# RF.net
KiCad netlist of a schematic drawn in Altium Designer
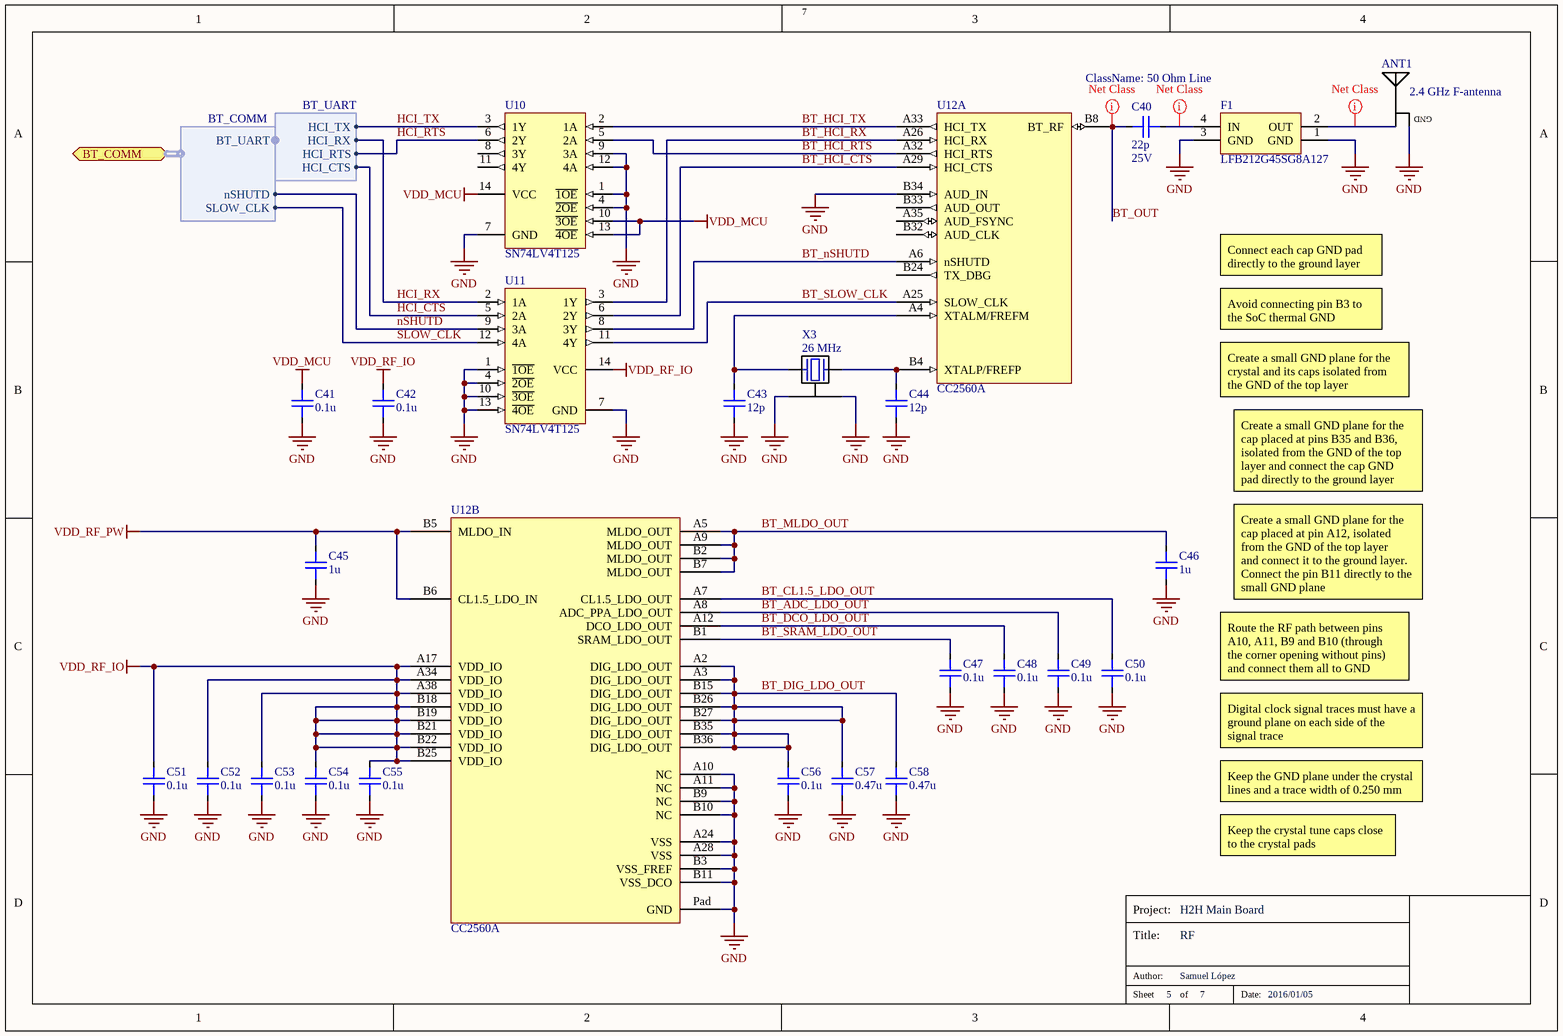
[diagram p0: RF.SchDoc]

(export (version "E")
  (design (tool "Eeschema 10.0.6"))
  (components
    (comp (ref "ANT1")
      (value "2.4 GHz F-antenna")
      (footprint "Antenna Inverted F 2.4 GHz")
      (description "Antenna - Inverted F 2.4 GHz")
      (libsource (lib "H2H") (part "ANT 2.4 GHz"))
    )
    (comp (ref "C40")
      (value "22p")
      (footprint "C0402")
      (description "Capacitor")
      (fields (field (name "RATED VOLTAGE") "25V"))
      (libsource (lib "Misc") (part "Capacitor"))
    )
    (comp (ref "C41")
      (value "0.1u")
      (footprint "C0603")
      (description "Capacitor")
      (libsource (lib "Misc") (part "Capacitor"))
    )
    (comp (ref "C42")
      (value "0.1u")
      (footprint "C0603")
      (description "Capacitor")
      (libsource (lib "Misc") (part "Capacitor"))
    )
    (comp (ref "C43")
      (value "12p")
      (footprint "C0402")
      (description "Capacitor")
      (libsource (lib "Misc") (part "Capacitor"))
    )
    (comp (ref "C44")
      (value "12p")
      (footprint "C0402")
      (description "Capacitor")
      (libsource (lib "Misc") (part "Capacitor"))
    )
    (comp (ref "C45")
      (value "1u")
      (footprint "C0402")
      (description "Capacitor")
      (libsource (lib "Misc") (part "Capacitor"))
    )
    (comp (ref "C46")
      (value "1u")
      (footprint "C0402")
      (description "Capacitor")
      (libsource (lib "Misc") (part "Capacitor"))
    )
    (comp (ref "C47")
      (value "0.1u")
      (footprint "C0402")
      (description "Capacitor")
      (libsource (lib "Misc") (part "Capacitor"))
    )
    (comp (ref "C48")
      (value "0.1u")
      (footprint "C0402")
      (description "Capacitor")
      (libsource (lib "Misc") (part "Capacitor"))
    )
    (comp (ref "C49")
      (value "0.1u")
      (footprint "C0402")
      (description "Capacitor")
      (libsource (lib "Misc") (part "Capacitor"))
    )
    (comp (ref "C50")
      (value "0.1u")
      (footprint "C0402")
      (description "Capacitor")
      (libsource (lib "Misc") (part "Capacitor"))
    )
    (comp (ref "C51")
      (value "0.1u")
      (footprint "C0402")
      (description "Capacitor")
      (libsource (lib "Misc") (part "Capacitor"))
    )
    (comp (ref "C52")
      (value "0.1u")
      (footprint "C0402")
      (description "Capacitor")
      (libsource (lib "Misc") (part "Capacitor"))
    )
    (comp (ref "C53")
      (value "0.1u")
      (footprint "C0402")
      (description "Capacitor")
      (libsource (lib "Misc") (part "Capacitor"))
    )
    (comp (ref "C54")
      (value "0.1u")
      (footprint "C0402")
      (description "Capacitor")
      (libsource (lib "Misc") (part "Capacitor"))
    )
    (comp (ref "C55")
      (value "0.1u")
      (footprint "C0402")
      (description "Capacitor")
      (libsource (lib "Misc") (part "Capacitor"))
    )
    (comp (ref "C56")
      (value "0.1u")
      (footprint "C0402")
      (description "Capacitor")
      (libsource (lib "Misc") (part "Capacitor"))
    )
    (comp (ref "C57")
      (value "0.47u")
      (footprint "C0402")
      (description "Capacitor")
      (libsource (lib "Misc") (part "Capacitor"))
    )
    (comp (ref "C58")
      (value "0.47u")
      (footprint "C0402")
      (description "Capacitor")
      (libsource (lib "Misc") (part "Capacitor"))
    )
    (comp (ref "F1")
      (value "LFB212G45SG8A127")
      (footprint "LFB212G45SG8A127")
      (description "Filter - RF 2.4 GHz")
      (libsource (lib "H2H") (part "LFB212G45SG8A127"))
    )
    (comp (ref "U10")
      (value "SN74LV4T125")
      (footprint "SN74LV4T125")
      (description "IC - Voltage Level Translator")
      (libsource (lib "") (part "SN74LV4T125_1"))
    )
    (comp (ref "U11")
      (value "SN74LV4T125")
      (footprint "SN74LV4T125")
      (description "IC - Voltage Level Translator")
      (libsource (lib "H2H") (part "SN74LV4T125"))
    )
    (comp (ref "U12")
      (value "CC2560A")
      (footprint "CC256x")
      (description "IC - Bluetooth 4.0 controller (BR/EDR)")
      (libsource (lib "H2H") (part "CC2560A"))
    )
    (comp (ref "X3")
      (value "NX2016SA")
      (footprint "NX2016SA")
      (description "Crystal - 26 MHz")
      (fields (field (name "FREQUENCY") "26 MHz"))
      (libsource (lib "H2H") (part "NX2016SA"))
    )
  )
  (nets
    (net (code "2") (name "/BT_ADC_LDO_OUT") (class "Default")
      (node (ref "C49") (pin "2") (pinfunction "2_2") (pintype "passive"))
      (node (ref "U12") (pin "A8") (pinfunction "ADC_PPA_LDO_OUT_A8") (pintype "power_in"))
    )
    (net (code "3") (name "/BT_CL1.5_LDO_OUT") (class "Default")
      (node (ref "C50") (pin "2") (pinfunction "2_2") (pintype "passive"))
      (node (ref "U12") (pin "A7") (pinfunction "CL1.5_LDO_OUT_A7") (pintype "power_in"))
    )
    (net (code "4") (name "/BT_DCO_LDO_OUT") (class "Default")
      (node (ref "C48") (pin "2") (pinfunction "2_2") (pintype "passive"))
      (node (ref "U12") (pin "A12") (pinfunction "DCO_LDO_OUT_A12") (pintype "power_in"))
    )
    (net (code "5") (name "/BT_DIG_LDO_OUT") (class "Default")
      (node (ref "C56") (pin "2") (pinfunction "2_2") (pintype "passive"))
      (node (ref "C57") (pin "2") (pinfunction "2_2") (pintype "passive"))
      (node (ref "C58") (pin "2") (pinfunction "2_2") (pintype "passive"))
      (node (ref "U12") (pin "A2") (pinfunction "DIG_LDO_OUT_A2") (pintype "power_in"))
      (node (ref "U12") (pin "A3") (pinfunction "DIG_LDO_OUT_A3") (pintype "power_in"))
      (node (ref "U12") (pin "B15") (pinfunction "DIG_LDO_OUT_B15") (pintype "power_in"))
      (node (ref "U12") (pin "B26") (pinfunction "DIG_LDO_OUT_B26") (pintype "power_in"))
      (node (ref "U12") (pin "B27") (pinfunction "DIG_LDO_OUT_B27") (pintype "power_in"))
      (node (ref "U12") (pin "B35") (pinfunction "DIG_LDO_OUT_B35") (pintype "power_in"))
      (node (ref "U12") (pin "B36") (pinfunction "DIG_LDO_OUT_B36") (pintype "power_in"))
    )
    (net (code "6") (name "/BT_HCI_CTS") (class "Default")
      (node (ref "U11") (pin "6") (pinfunction "2Y_6") (pintype "output"))
      (node (ref "U12") (pin "A29") (pinfunction "HCI_CTS_A29") (pintype "input"))
    )
    (net (code "7") (name "/BT_HCI_RTS") (class "Default")
      (node (ref "U10") (pin "5") (pinfunction "2A_5") (pintype "input"))
      (node (ref "U12") (pin "A32") (pinfunction "HCI_RTS_A32") (pintype "output"))
    )
    (net (code "8") (name "/BT_HCI_RX") (class "Default")
      (node (ref "U11") (pin "3") (pinfunction "1Y_3") (pintype "output"))
      (node (ref "U12") (pin "A26") (pinfunction "HCI_RX_A26") (pintype "input"))
    )
    (net (code "9") (name "/BT_HCI_TX") (class "Default")
      (node (ref "U10") (pin "2") (pinfunction "1A_2") (pintype "input"))
      (node (ref "U12") (pin "A33") (pinfunction "HCI_TX_A33") (pintype "output"))
    )
    (net (code "10") (name "/BT_MLDO_OUT") (class "Default")
      (node (ref "C46") (pin "2") (pinfunction "2_2") (pintype "passive"))
      (node (ref "U12") (pin "A5") (pinfunction "MLDO_OUT_A5") (pintype "power_in"))
      (node (ref "U12") (pin "A9") (pinfunction "MLDO_OUT_A9") (pintype "power_in"))
      (node (ref "U12") (pin "B2") (pinfunction "MLDO_OUT_B2") (pintype "power_in"))
      (node (ref "U12") (pin "B7") (pinfunction "MLDO_OUT_B7") (pintype "power_in"))
    )
    (net (code "11") (name "/BT_OUT") (class "Default")
      (node (ref "C40") (pin "1") (pinfunction "1_1") (pintype "passive"))
      (node (ref "U12") (pin "B8") (pinfunction "BT_RF_B8") (pintype "bidirectional"))
    )
    (net (code "12") (name "/BT_SLOW_CLK") (class "Default")
      (node (ref "U11") (pin "11") (pinfunction "4Y_11") (pintype "output"))
      (node (ref "U12") (pin "A25") (pinfunction "SLOW_CLK_A25") (pintype "input"))
    )
    (net (code "13") (name "/BT_SRAM_LDO_OUT") (class "Default")
      (node (ref "C47") (pin "2") (pinfunction "2_2") (pintype "passive"))
      (node (ref "U12") (pin "B1") (pinfunction "SRAM_LDO_OUT_B1") (pintype "power_in"))
    )
    (net (code "14") (name "/BT_nSHUTD") (class "Default")
      (node (ref "U11") (pin "8") (pinfunction "3Y_8") (pintype "output"))
      (node (ref "U12") (pin "A6") (pinfunction "nSHUTD_A6") (pintype "input"))
    )
    (net (code "15") (name "/HCI_CTS") (class "Default")
      (node (ref "U11") (pin "5") (pinfunction "2A_5") (pintype "input"))
    )
    (net (code "16") (name "/HCI_RTS") (class "Default")
      (node (ref "U10") (pin "6") (pinfunction "2Y_6") (pintype "output"))
    )
    (net (code "17") (name "/HCI_RX") (class "Default")
      (node (ref "U11") (pin "2") (pinfunction "1A_2") (pintype "input"))
    )
    (net (code "18") (name "/HCI_TX") (class "Default")
      (node (ref "U10") (pin "3") (pinfunction "1Y_3") (pintype "output"))
    )
    (net (code "19") (name "/SLOW_CLK") (class "Default")
      (node (ref "U11") (pin "12") (pinfunction "4A_12") (pintype "input"))
    )
    (net (code "20") (name "/nSHUTD") (class "Default")
      (node (ref "U11") (pin "9") (pinfunction "3A_9") (pintype "input"))
    )
    (net (code "22") (name "GND") (class "Default")
      (node (ref "ANT1") (pin "2") (pinfunction "GND_2") (pintype "passive"))
      (node (ref "C41") (pin "1") (pinfunction "1_1") (pintype "passive"))
      (node (ref "C42") (pin "1") (pinfunction "1_1") (pintype "passive"))
      (node (ref "C43") (pin "1") (pinfunction "1_1") (pintype "passive"))
      (node (ref "C44") (pin "1") (pinfunction "1_1") (pintype "passive"))
      (node (ref "C45") (pin "1") (pinfunction "1_1") (pintype "passive"))
      (node (ref "C46") (pin "1") (pinfunction "1_1") (pintype "passive"))
      (node (ref "C47") (pin "1") (pinfunction "1_1") (pintype "passive"))
      (node (ref "C48") (pin "1") (pinfunction "1_1") (pintype "passive"))
      (node (ref "C49") (pin "1") (pinfunction "1_1") (pintype "passive"))
      (node (ref "C50") (pin "1") (pinfunction "1_1") (pintype "passive"))
      (node (ref "C51") (pin "1") (pinfunction "1_1") (pintype "passive"))
      (node (ref "C52") (pin "1") (pinfunction "1_1") (pintype "passive"))
      (node (ref "C53") (pin "1") (pinfunction "1_1") (pintype "passive"))
      (node (ref "C54") (pin "1") (pinfunction "1_1") (pintype "passive"))
      (node (ref "C55") (pin "1") (pinfunction "1_1") (pintype "passive"))
      (node (ref "C56") (pin "1") (pinfunction "1_1") (pintype "passive"))
      (node (ref "C57") (pin "1") (pinfunction "1_1") (pintype "passive"))
      (node (ref "C58") (pin "1") (pinfunction "1_1") (pintype "passive"))
      (node (ref "F1") (pin "1") (pinfunction "GND_1") (pintype "power_in"))
      (node (ref "F1") (pin "3") (pinfunction "GND_3") (pintype "power_in"))
      (node (ref "U10") (pin "1") (pinfunction "~{1OE}_1") (pintype "input"))
      (node (ref "U10") (pin "12") (pinfunction "4A_12") (pintype "input"))
      (node (ref "U10") (pin "4") (pinfunction "~{2OE}_4") (pintype "input"))
      (node (ref "U10") (pin "7") (pinfunction "GND_7") (pintype "power_in"))
      (node (ref "U10") (pin "9") (pinfunction "3A_9") (pintype "input"))
      (node (ref "U11") (pin "1") (pinfunction "~{1OE}_1") (pintype "input"))
      (node (ref "U11") (pin "10") (pinfunction "~{3OE}_10") (pintype "input"))
      (node (ref "U11") (pin "13") (pinfunction "~{4OE}_13") (pintype "input"))
      (node (ref "U11") (pin "4") (pinfunction "~{2OE}_4") (pintype "input"))
      (node (ref "U11") (pin "7") (pinfunction "GND_7") (pintype "power_in"))
      (node (ref "U12") (pin "A10") (pinfunction "NC_A10") (pintype "passive"))
      (node (ref "U12") (pin "A11") (pinfunction "NC_A11") (pintype "passive"))
      (node (ref "U12") (pin "A24") (pinfunction "VSS_A24") (pintype "power_in"))
      (node (ref "U12") (pin "A28") (pinfunction "VSS_A28") (pintype "power_in"))
      (node (ref "U12") (pin "B10") (pinfunction "NC_B10") (pintype "passive"))
      (node (ref "U12") (pin "B11") (pinfunction "VSS_DCO_B11") (pintype "power_in"))
      (node (ref "U12") (pin "B3") (pinfunction "VSS_FREF_B3") (pintype "power_in"))
      (node (ref "U12") (pin "B34") (pinfunction "AUD_IN_B34") (pintype "input"))
      (node (ref "U12") (pin "B9") (pinfunction "NC_B9") (pintype "passive"))
      (node (ref "U12") (pin "Pad") (pinfunction "GND_Pad") (pintype "power_in"))
      (node (ref "X3") (pin "2") (pinfunction "2_2") (pintype "passive"))
      (node (ref "X3") (pin "4") (pinfunction "4_4") (pintype "passive"))
    )
    (net (code "23") (name "Net-(ANT1-IN)") (class "Default")
      (node (ref "ANT1") (pin "1") (pinfunction "IN_1") (pintype "passive"))
      (node (ref "F1") (pin "2") (pinfunction "OUT_2") (pintype "passive"))
    )
    (net (code "24") (name "Net-(F1-IN)") (class "Default")
      (node (ref "C40") (pin "2") (pinfunction "2_2") (pintype "passive"))
      (node (ref "F1") (pin "4") (pinfunction "IN_4") (pintype "power_in"))
    )
    (net (code "25") (name "Net-(U12A-XTALM{slash}FREFM)") (class "Default")
      (node (ref "C43") (pin "2") (pinfunction "2_2") (pintype "passive"))
      (node (ref "U12") (pin "A4") (pinfunction "XTALM/FREFM_A4") (pintype "input"))
      (node (ref "X3") (pin "1") (pinfunction "1_1") (pintype "passive"))
    )
    (net (code "26") (name "Net-(U12A-XTALP{slash}FREFP)") (class "Default")
      (node (ref "C44") (pin "2") (pinfunction "2_2") (pintype "passive"))
      (node (ref "U12") (pin "B4") (pinfunction "XTALP/FREFP_B4") (pintype "input"))
      (node (ref "X3") (pin "3") (pinfunction "3_3") (pintype "passive"))
    )
    (net (code "27") (name "VDD_MCU") (class "Default")
      (node (ref "C41") (pin "2") (pinfunction "2_2") (pintype "passive"))
      (node (ref "U10") (pin "10") (pinfunction "~{3OE}_10") (pintype "input"))
      (node (ref "U10") (pin "13") (pinfunction "~{4OE}_13") (pintype "input"))
      (node (ref "U10") (pin "14") (pinfunction "VCC_14") (pintype "power_in"))
    )
    (net (code "28") (name "VDD_RF_IO") (class "Default")
      (node (ref "C42") (pin "2") (pinfunction "2_2") (pintype "passive"))
      (node (ref "C51") (pin "2") (pinfunction "2_2") (pintype "passive"))
      (node (ref "C52") (pin "2") (pinfunction "2_2") (pintype "passive"))
      (node (ref "C53") (pin "2") (pinfunction "2_2") (pintype "passive"))
      (node (ref "C54") (pin "2") (pinfunction "2_2") (pintype "passive"))
      (node (ref "C55") (pin "2") (pinfunction "2_2") (pintype "passive"))
      (node (ref "U11") (pin "14") (pinfunction "VCC_14") (pintype "power_in"))
      (node (ref "U12") (pin "A17") (pinfunction "VDD_IO_A17") (pintype "power_in"))
      (node (ref "U12") (pin "A34") (pinfunction "VDD_IO_A34") (pintype "power_in"))
      (node (ref "U12") (pin "A38") (pinfunction "VDD_IO_A38") (pintype "power_in"))
      (node (ref "U12") (pin "B18") (pinfunction "VDD_IO_B18") (pintype "power_in"))
      (node (ref "U12") (pin "B19") (pinfunction "VDD_IO_B19") (pintype "power_in"))
      (node (ref "U12") (pin "B21") (pinfunction "VDD_IO_B21") (pintype "power_in"))
      (node (ref "U12") (pin "B22") (pinfunction "VDD_IO_B22") (pintype "power_in"))
      (node (ref "U12") (pin "B25") (pinfunction "VDD_IO_B25") (pintype "power_in"))
    )
    (net (code "29") (name "VDD_RF_PW") (class "Default")
      (node (ref "C45") (pin "2") (pinfunction "2_2") (pintype "passive"))
      (node (ref "U12") (pin "B5") (pinfunction "MLDO_IN_B5") (pintype "power_in"))
      (node (ref "U12") (pin "B6") (pinfunction "CL1.5_LDO_IN_B6") (pintype "power_in"))
    )
    (net (code "30") (name "unconnected-(U10-3Y-Pad8)") (class "Default")
      (node (ref "U10") (pin "8") (pinfunction "3Y_8") (pintype "output"))
    )
    (net (code "31") (name "unconnected-(U10-4Y-Pad11)") (class "Default")
      (node (ref "U10") (pin "11") (pinfunction "4Y_11") (pintype "output"))
    )
    (net (code "32") (name "unconnected-(U12A-AUD_CLK-PadB32)") (class "Default")
      (node (ref "U12") (pin "B32") (pinfunction "AUD_CLK_B32") (pintype "bidirectional"))
    )
    (net (code "33") (name "unconnected-(U12A-AUD_FSYNC-PadA35)") (class "Default")
      (node (ref "U12") (pin "A35") (pinfunction "AUD_FSYNC_A35") (pintype "bidirectional"))
    )
    (net (code "34") (name "unconnected-(U12A-AUD_OUT-PadB33)") (class "Default")
      (node (ref "U12") (pin "B33") (pinfunction "AUD_OUT_B33") (pintype "output"))
    )
    (net (code "35") (name "unconnected-(U12A-TX_DBG-PadB24)") (class "Default")
      (node (ref "U12") (pin "B24") (pinfunction "TX_DBG_B24") (pintype "output"))
    )
  )
)
